# user_interface_bf_2_2_1.net
KiCad netlist of a schematic drawn in EAGLE
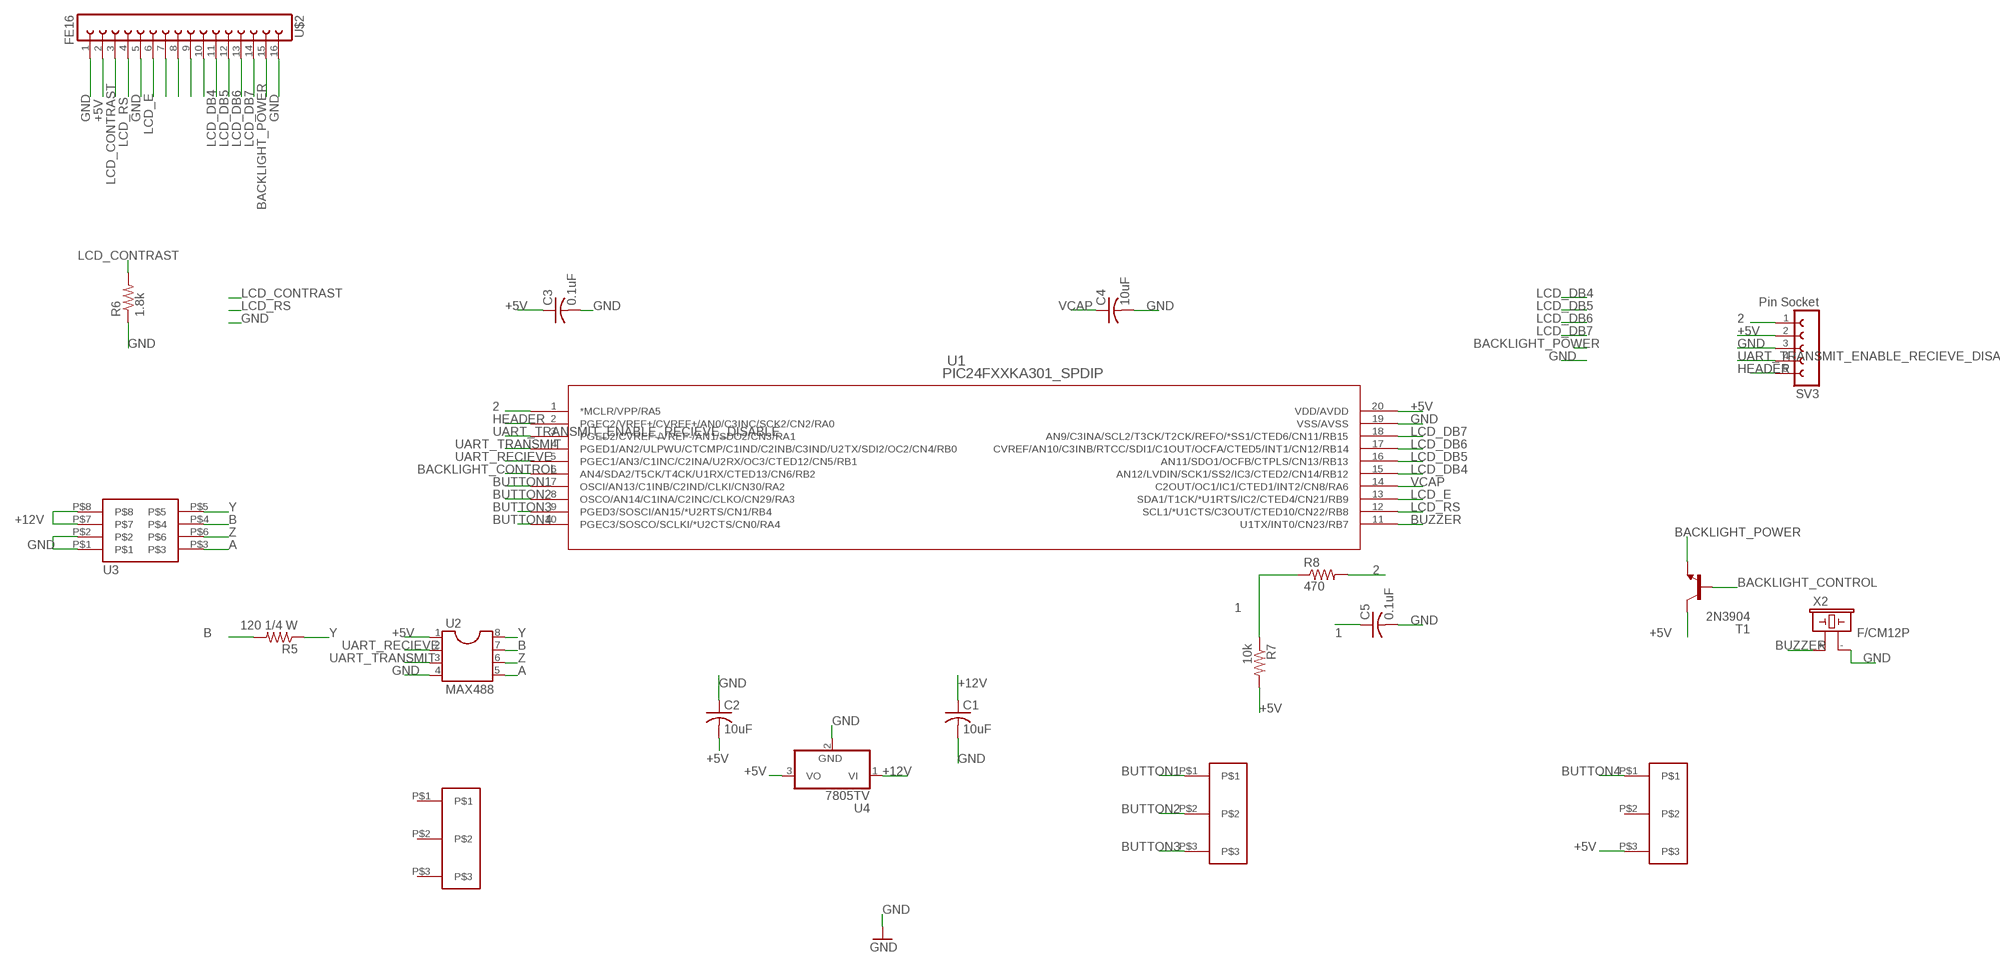
[diagram p0: schematic, sheet 1]

(export (version "E")
  (design (tool "Eeschema 10.0.6"))
  (components
    (comp (ref "C1")
      (value "10uF")
      (footprint "eagle-import:C050-025X075")
      (libsource (lib "eagle-import") (part "C-US050-025X075"))
    )
    (comp (ref "C2")
      (value "10uF")
      (footprint "eagle-import:C050-025X075")
      (libsource (lib "eagle-import") (part "C-US050-025X075"))
    )
    (comp (ref "C3")
      (value "0.1uF")
      (footprint "eagle-import:C050-025X075")
      (libsource (lib "eagle-import") (part "C-US050-025X075"))
    )
    (comp (ref "C4")
      (value "10uF")
      (footprint "eagle-import:C050-025X075")
      (libsource (lib "eagle-import") (part "C-US050-025X075"))
    )
    (comp (ref "C5")
      (value "0.1uF")
      (footprint "eagle-import:C050-025X075")
      (libsource (lib "eagle-import") (part "C-US050-025X075"))
    )
    (comp (ref "R5")
      (value "120 1/4 W")
      (footprint "eagle-import:0207_10")
      (libsource (lib "eagle-import") (part "R-US_0207/10"))
    )
    (comp (ref "R6")
      (value "1.8k")
      (footprint "eagle-import:0207_10")
      (libsource (lib "eagle-import") (part "R-US_0207/10"))
    )
    (comp (ref "R7")
      (value "10k")
      (footprint "eagle-import:0207_10")
      (libsource (lib "eagle-import") (part "R-US_0207/10"))
    )
    (comp (ref "R8")
      (value "470")
      (footprint "eagle-import:0207_10")
      (libsource (lib "eagle-import") (part "R-US_0207/10"))
    )
    (comp (ref "SV3")
      (value "Pin Socket")
      (footprint "eagle-import:FE05-1")
      (libsource (lib "eagle-import") (part "FE05-1"))
    )
    (comp (ref "T1")
      (value "2N3904")
      (footprint "eagle-import:TO92")
      (libsource (lib "eagle-import") (part "2N3904"))
    )
    (comp (ref "U$2")
      (value "FE16")
      (footprint "eagle-import:FE16")
      (libsource (lib "eagle-import") (part "FE16"))
    )
    (comp (ref "U$4")
      (value "3_PIN_FEMALE_HEADER")
      (footprint "eagle-import:3_PIN_FEMALE_HEADER")
      (libsource (lib "eagle-import") (part "3_PIN_FEMALE_HEADER"))
    )
    (comp (ref "U1")
      (value "PIC24FXXKA301_SPDIP")
      (footprint "eagle-import:SPDIP20_300MC")
      (libsource (lib "eagle-import") (part "PIC24FXXKA301_SPDIP"))
    )
    (comp (ref "U2")
      (value "MAX488")
      (footprint "eagle-import:DIL08")
      (libsource (lib "eagle-import") (part "DIL8"))
    )
    (comp (ref "U3")
      (value "CAT5")
      (footprint "eagle-import:CAT5")
      (libsource (lib "eagle-import") (part "CAT5"))
    )
    (comp (ref "U4")
      (value "7805TV")
      (footprint "eagle-import:TO220V")
      (libsource (lib "eagle-import") (part "78TV05"))
    )
    (comp (ref "U6")
      (value "3_PIN_FEMALE_HEADER")
      (footprint "eagle-import:3_PIN_FEMALE_HEADER")
      (libsource (lib "eagle-import") (part "3_PIN_FEMALE_HEADER"))
    )
    (comp (ref "U7")
      (value "3_PIN_FEMALE_HEADER")
      (footprint "eagle-import:3_PIN_FEMALE_HEADER")
      (libsource (lib "eagle-import") (part "3_PIN_FEMALE_HEADER"))
    )
    (comp (ref "X2")
      (value "F/CM12P")
      (footprint "eagle-import:F_CM12P")
      (libsource (lib "eagle-import") (part "F/CM12P"))
    )
  )
  (nets
    (net (code "1") (name "/+5V") (class "Default")
      (node (ref "C2") (pin "2") (pinfunction "2_2") (pintype "passive"))
      (node (ref "C3") (pin "1") (pinfunction "1_1") (pintype "passive"))
      (node (ref "R7") (pin "2") (pinfunction "2_2") (pintype "passive"))
      (node (ref "SV3") (pin "2") (pinfunction "2_2") (pintype "passive"))
      (node (ref "T1") (pin "1") (pinfunction "C_1") (pintype "passive"))
      (node (ref "U$2") (pin "2") (pinfunction "2_2") (pintype "passive"))
      (node (ref "U1") (pin "20") (pinfunction "VDD/AVDD_20") (pintype "passive"))
      (node (ref "U2") (pin "1") (pinfunction "1_1") (pintype "passive"))
      (node (ref "U4") (pin "3") (pinfunction "VO_3") (pintype "passive"))
      (node (ref "U7") (pin "P$3") (pinfunction "P$3_P$3") (pintype "bidirectional"))
    )
    (net (code "2") (name "/+12V") (class "Default")
      (node (ref "C1") (pin "1") (pinfunction "1_1") (pintype "passive"))
      (node (ref "U3") (pin "P$7") (pinfunction "P$7_P$7") (pintype "bidirectional"))
      (node (ref "U3") (pin "P$8") (pinfunction "P$8_P$8") (pintype "bidirectional"))
      (node (ref "U4") (pin "1") (pinfunction "VI_1") (pintype "input"))
    )
    (net (code "3") (name "/1") (class "Default")
      (node (ref "C5") (pin "1") (pinfunction "1_1") (pintype "passive"))
      (node (ref "R7") (pin "1") (pinfunction "1_1") (pintype "passive"))
      (node (ref "R8") (pin "1") (pinfunction "1_1") (pintype "passive"))
    )
    (net (code "4") (name "/2") (class "Default")
      (node (ref "R8") (pin "2") (pinfunction "2_2") (pintype "passive"))
      (node (ref "SV3") (pin "1") (pinfunction "1_1") (pintype "passive"))
      (node (ref "U1") (pin "1") (pinfunction "*MCLR/VPP/RA5_1") (pintype "passive"))
    )
    (net (code "5") (name "/A") (class "Default")
      (node (ref "U2") (pin "5") (pinfunction "5_5") (pintype "passive"))
      (node (ref "U3") (pin "P$3") (pinfunction "P$3_P$3") (pintype "bidirectional"))
    )
    (net (code "6") (name "/B") (class "Default")
      (node (ref "R5") (pin "2") (pinfunction "2_2") (pintype "passive"))
      (node (ref "U2") (pin "7") (pinfunction "7_7") (pintype "passive"))
      (node (ref "U3") (pin "P$4") (pinfunction "P$4_P$4") (pintype "bidirectional"))
    )
    (net (code "7") (name "/BACKLIGHT_CONTROL") (class "Default")
      (node (ref "T1") (pin "2") (pinfunction "B_2") (pintype "passive"))
      (node (ref "U1") (pin "6") (pinfunction "AN4/SDA2/T5CK/T4CK/U1RX/CTED13/CN6/RB2_6") (pintype "passive"))
    )
    (net (code "8") (name "/BACKLIGHT_POWER") (class "Default")
      (node (ref "T1") (pin "3") (pinfunction "E_3") (pintype "passive"))
      (node (ref "U$2") (pin "15") (pinfunction "15_15") (pintype "passive"))
    )
    (net (code "9") (name "/BUTTON1") (class "Default")
      (node (ref "U1") (pin "7") (pinfunction "OSCI/AN13/C1INB/C2IND/CLKI/CN30/RA2_7") (pintype "passive"))
      (node (ref "U6") (pin "P$1") (pinfunction "P$1_P$1") (pintype "bidirectional"))
    )
    (net (code "10") (name "/BUTTON2") (class "Default")
      (node (ref "U1") (pin "8") (pinfunction "OSCO/AN14/C1INA/C2INC/CLKO/CN29/RA3_8") (pintype "passive"))
      (node (ref "U6") (pin "P$2") (pinfunction "P$2_P$2") (pintype "bidirectional"))
    )
    (net (code "11") (name "/BUTTON3") (class "Default")
      (node (ref "U1") (pin "9") (pinfunction "PGED3/SOSCI/AN15/*U2RTS/CN1/RB4_9") (pintype "passive"))
      (node (ref "U6") (pin "P$3") (pinfunction "P$3_P$3") (pintype "bidirectional"))
    )
    (net (code "12") (name "/BUTTON4") (class "Default")
      (node (ref "U1") (pin "10") (pinfunction "PGEC3/SOSCO/SCLKI/*U2CTS/CN0/RA4_10") (pintype "passive"))
      (node (ref "U7") (pin "P$1") (pinfunction "P$1_P$1") (pintype "bidirectional"))
    )
    (net (code "13") (name "/BUZZER") (class "Default")
      (node (ref "U1") (pin "11") (pinfunction "U1TX/INT0/CN23/RB7_11") (pintype "passive"))
      (node (ref "X2") (pin "+") (pinfunction "1_+") (pintype "passive"))
    )
    (net (code "14") (name "/HEADER") (class "Default")
      (node (ref "SV3") (pin "5") (pinfunction "5_5") (pintype "passive"))
      (node (ref "U1") (pin "2") (pinfunction "PGEC2/VREF+/CVREF+/AN0/C3INC/SCK2/CN2/RA0_2") (pintype "passive"))
    )
    (net (code "15") (name "/LCD_CONTRAST") (class "Default")
      (node (ref "R6") (pin "2") (pinfunction "2_2") (pintype "passive"))
      (node (ref "U$2") (pin "3") (pinfunction "3_3") (pintype "passive"))
    )
    (net (code "16") (name "/LCD_DB4") (class "Default")
      (node (ref "U$2") (pin "11") (pinfunction "11_11") (pintype "passive"))
      (node (ref "U1") (pin "15") (pinfunction "AN12/LVDIN/SCK1/SS2/IC3/CTED2/CN14/RB12_15") (pintype "passive"))
    )
    (net (code "17") (name "/LCD_DB5") (class "Default")
      (node (ref "U$2") (pin "12") (pinfunction "12_12") (pintype "passive"))
      (node (ref "U1") (pin "16") (pinfunction "AN11/SDO1/OCFB/CTPLS/CN13/RB13_16") (pintype "passive"))
    )
    (net (code "18") (name "/LCD_DB6") (class "Default")
      (node (ref "U$2") (pin "13") (pinfunction "13_13") (pintype "passive"))
      (node (ref "U1") (pin "17") (pinfunction "CVREF/AN10/C3INB/RTCC/SDI1/C1OUT/OCFA/CTED5/INT1/CN12/RB14_17") (pintype "passive"))
    )
    (net (code "19") (name "/LCD_DB7") (class "Default")
      (node (ref "U$2") (pin "14") (pinfunction "14_14") (pintype "passive"))
      (node (ref "U1") (pin "18") (pinfunction "AN9/C3INA/SCL2/T3CK/T2CK/REFO/*SS1/CTED6/CN11/RB15_18") (pintype "passive"))
    )
    (net (code "20") (name "/LCD_E") (class "Default")
      (node (ref "U$2") (pin "6") (pinfunction "6_6") (pintype "passive"))
      (node (ref "U1") (pin "13") (pinfunction "SDA1/T1CK/*U1RTS/IC2/CTED4/CN21/RB9_13") (pintype "passive"))
    )
    (net (code "21") (name "/LCD_RS") (class "Default")
      (node (ref "U$2") (pin "4") (pinfunction "4_4") (pintype "passive"))
      (node (ref "U1") (pin "12") (pinfunction "SCL1/*U1CTS/C3OUT/CTED10/CN22/RB8_12") (pintype "passive"))
    )
    (net (code "22") (name "/UART_RECIEVE") (class "Default")
      (node (ref "U1") (pin "5") (pinfunction "PGEC1/AN3/C1INC/C2INA/U2RX/OC3/CTED12/CN5/RB1_5") (pintype "passive"))
      (node (ref "U2") (pin "2") (pinfunction "2_2") (pintype "passive"))
    )
    (net (code "23") (name "/UART_TRANSMIT") (class "Default")
      (node (ref "U1") (pin "4") (pinfunction "PGED1/AN2/ULPWU/CTCMP/C1IND/C2INB/C3IND/U2TX/SDI2/OC2/CN4/RB0_4") (pintype "passive"))
      (node (ref "U2") (pin "3") (pinfunction "3_3") (pintype "passive"))
    )
    (net (code "24") (name "/UART_TRANSMIT_ENABLE_RECIEVE_DISABLE") (class "Default")
      (node (ref "SV3") (pin "4") (pinfunction "4_4") (pintype "passive"))
      (node (ref "U1") (pin "3") (pinfunction "PGED2/CVREF-/VREF-/AN1/SDO2/CN3/RA1_3") (pintype "passive"))
    )
    (net (code "25") (name "/VCAP") (class "Default")
      (node (ref "C4") (pin "1") (pinfunction "1_1") (pintype "passive"))
      (node (ref "U1") (pin "14") (pinfunction "C2OUT/OC1/IC1/CTED1/INT2/CN8/RA6_14") (pintype "passive"))
    )
    (net (code "26") (name "/Y") (class "Default")
      (node (ref "R5") (pin "1") (pinfunction "1_1") (pintype "passive"))
      (node (ref "U2") (pin "8") (pinfunction "8_8") (pintype "passive"))
      (node (ref "U3") (pin "P$5") (pinfunction "P$5_P$5") (pintype "bidirectional"))
    )
    (net (code "27") (name "/Z") (class "Default")
      (node (ref "U2") (pin "6") (pinfunction "6_6") (pintype "passive"))
      (node (ref "U3") (pin "P$6") (pinfunction "P$6_P$6") (pintype "bidirectional"))
    )
    (net (code "28") (name "GND") (class "Default")
      (node (ref "C1") (pin "2") (pinfunction "2_2") (pintype "passive"))
      (node (ref "C2") (pin "1") (pinfunction "1_1") (pintype "passive"))
      (node (ref "C3") (pin "2") (pinfunction "2_2") (pintype "passive"))
      (node (ref "C4") (pin "2") (pinfunction "2_2") (pintype "passive"))
      (node (ref "C5") (pin "2") (pinfunction "2_2") (pintype "passive"))
      (node (ref "R6") (pin "1") (pinfunction "1_1") (pintype "passive"))
      (node (ref "SV3") (pin "3") (pinfunction "3_3") (pintype "passive"))
      (node (ref "U$2") (pin "1") (pinfunction "1_1") (pintype "passive"))
      (node (ref "U$2") (pin "16") (pinfunction "16_16") (pintype "passive"))
      (node (ref "U$2") (pin "5") (pinfunction "5_5") (pintype "passive"))
      (node (ref "U1") (pin "19") (pinfunction "VSS/AVSS_19") (pintype "passive"))
      (node (ref "U2") (pin "4") (pinfunction "4_4") (pintype "passive"))
      (node (ref "U3") (pin "P$1") (pinfunction "P$1_P$1") (pintype "bidirectional"))
      (node (ref "U3") (pin "P$2") (pinfunction "P$2_P$2") (pintype "bidirectional"))
      (node (ref "U4") (pin "2") (pinfunction "GND_2") (pintype "passive"))
      (node (ref "X2") (pin "-") (pinfunction "2_-") (pintype "passive"))
    )
    (net (code "29") (name "unconnected-(U$2-Pad7)") (class "Default")
      (node (ref "U$2") (pin "7") (pinfunction "7_7") (pintype "passive"))
    )
    (net (code "30") (name "unconnected-(U$2-Pad8)") (class "Default")
      (node (ref "U$2") (pin "8") (pinfunction "8_8") (pintype "passive"))
    )
    (net (code "31") (name "unconnected-(U$2-Pad9)") (class "Default")
      (node (ref "U$2") (pin "9") (pinfunction "9_9") (pintype "passive"))
    )
    (net (code "32") (name "unconnected-(U$2-Pad10)") (class "Default")
      (node (ref "U$2") (pin "10") (pinfunction "10_10") (pintype "passive"))
    )
    (net (code "33") (name "unconnected-(U$4-PadP$1)") (class "Default")
      (node (ref "U$4") (pin "P$1") (pinfunction "P$1_P$1") (pintype "bidirectional"))
    )
    (net (code "34") (name "unconnected-(U$4-PadP$2)") (class "Default")
      (node (ref "U$4") (pin "P$2") (pinfunction "P$2_P$2") (pintype "bidirectional"))
    )
    (net (code "35") (name "unconnected-(U$4-PadP$3)") (class "Default")
      (node (ref "U$4") (pin "P$3") (pinfunction "P$3_P$3") (pintype "bidirectional"))
    )
    (net (code "36") (name "unconnected-(U7-PadP$2)") (class "Default")
      (node (ref "U7") (pin "P$2") (pinfunction "P$2_P$2") (pintype "bidirectional"))
    )
  )
)
